# MicroController.net
KiCad netlist of a schematic drawn in Altium Designer
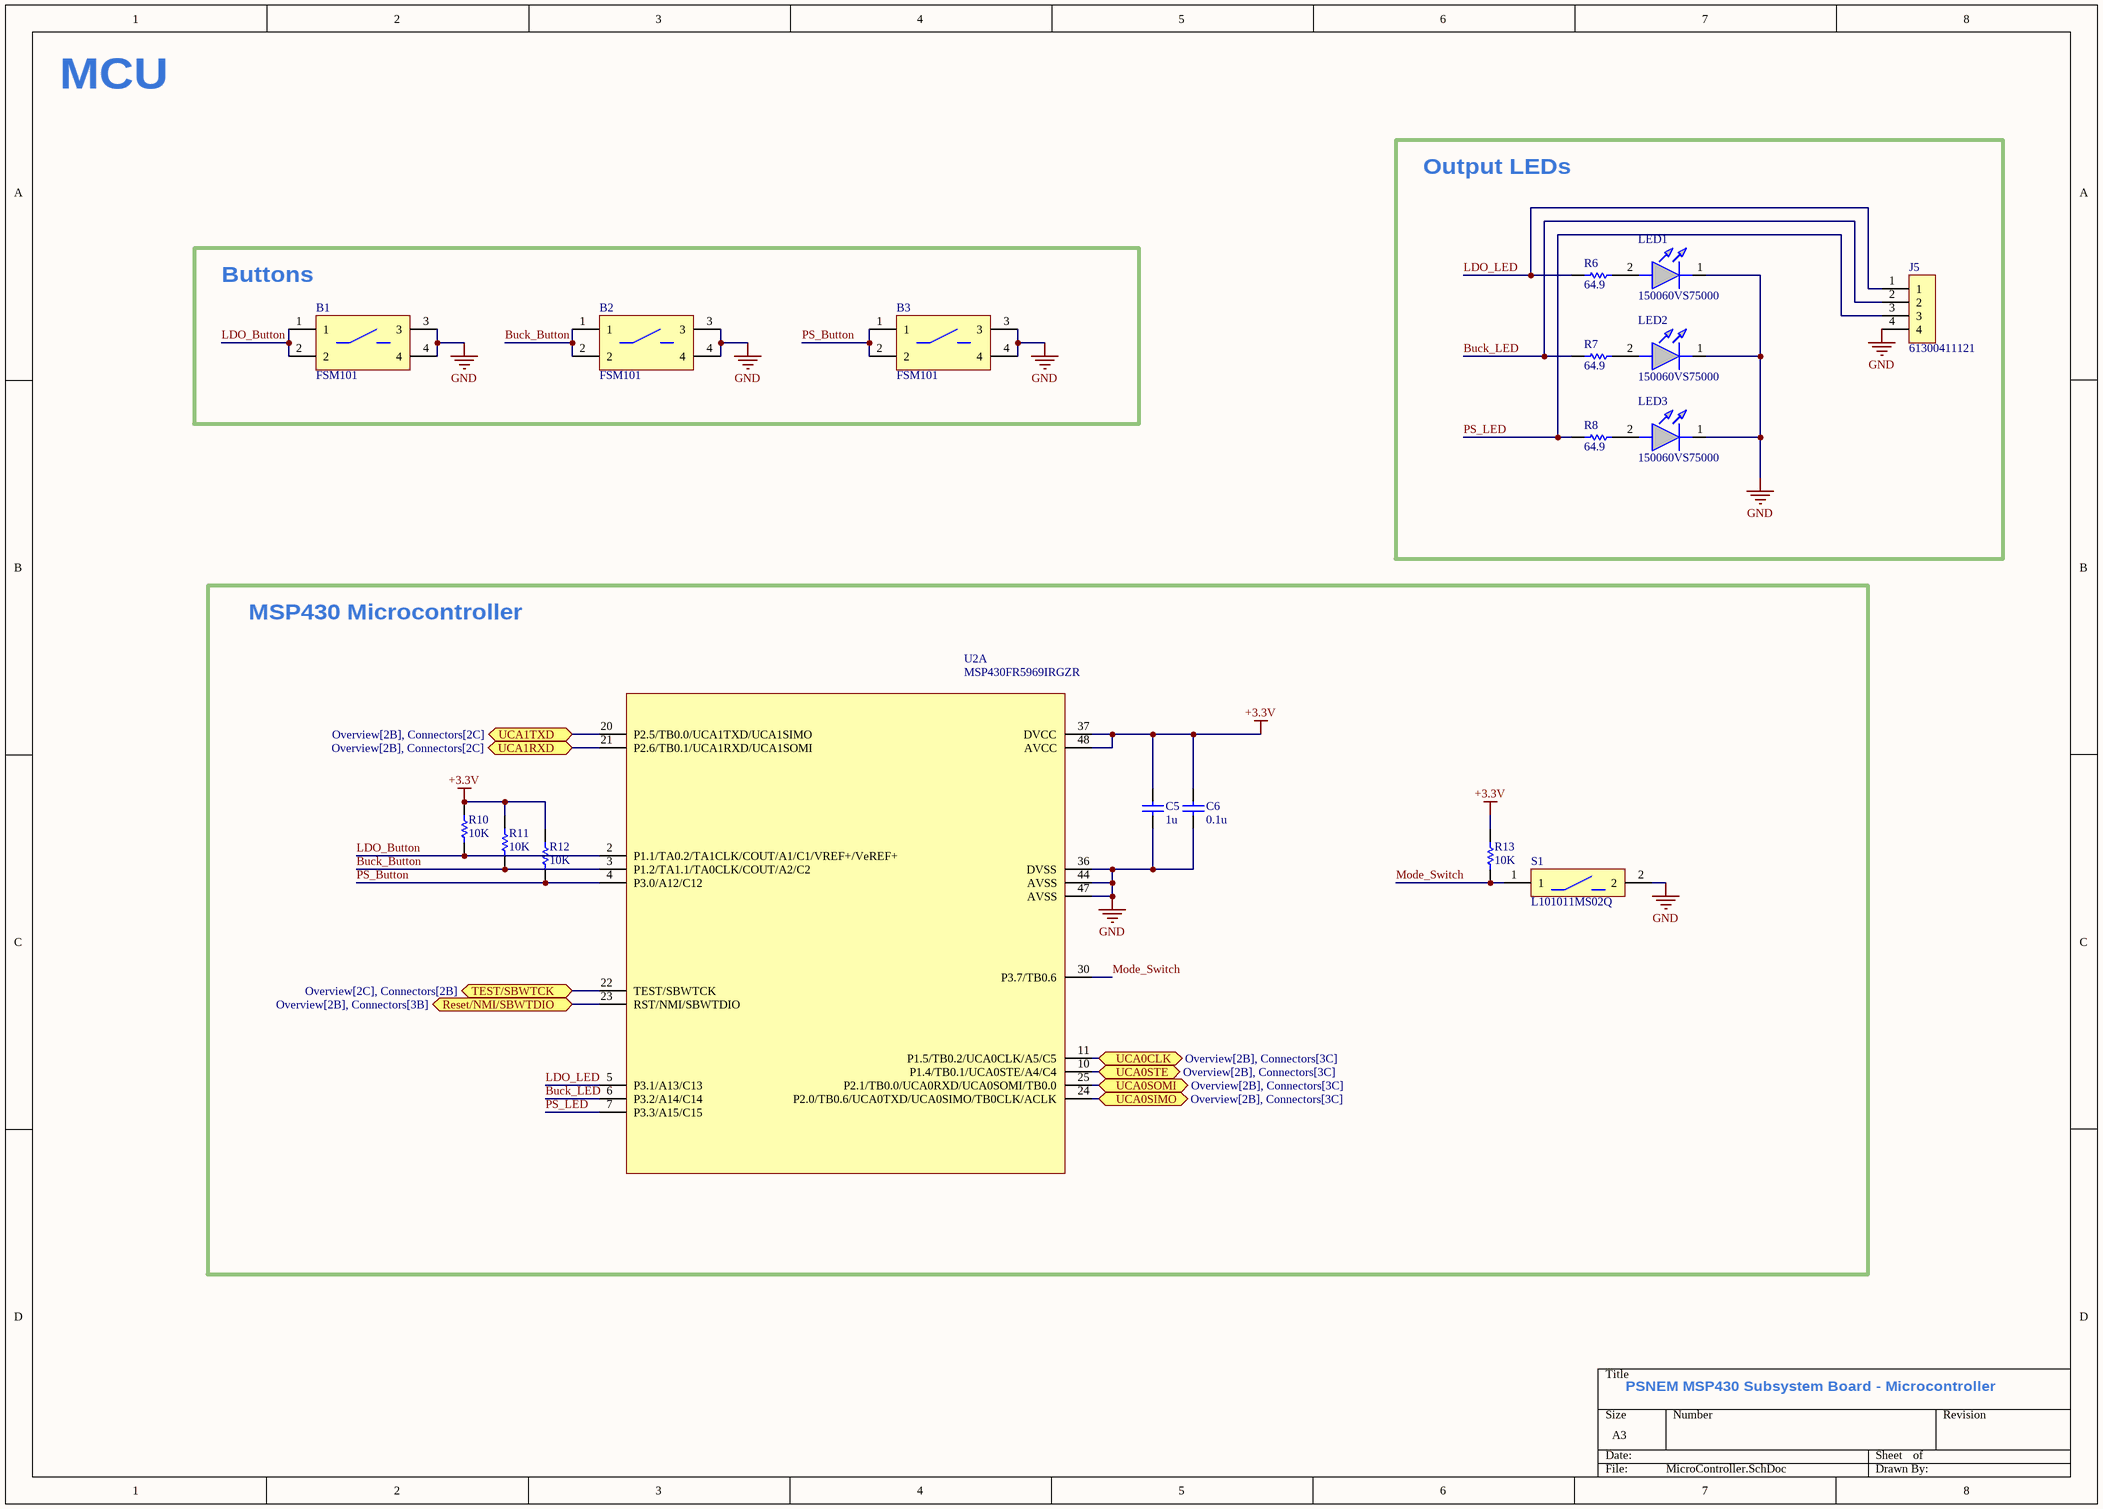
[diagram p0: MicroController.SchDoc]

(export (version "E")
  (design (tool "Eeschema 10.0.6"))
  (components
    (comp (ref "B1")
      (value "FSM101")
      (footprint "FSM101")
      (description "Tactile Switch SPST-NO Top Actuated Through Hole")
      (libsource (lib "Schlib1") (part "FSM101"))
    )
    (comp (ref "B2")
      (value "FSM101")
      (footprint "FSM101")
      (description "Tactile Switch SPST-NO Top Actuated Through Hole")
      (libsource (lib "Schlib1") (part "FSM101"))
    )
    (comp (ref "B3")
      (value "FSM101")
      (footprint "FSM101")
      (description "Tactile Switch SPST-NO Top Actuated Through Hole")
      (libsource (lib "Schlib1") (part "FSM101"))
    )
    (comp (ref "C5")
      (value "1u")
      (footprint "0805 Cap")
      (description "1 µF ±10% 16V Ceramic Capacitor X7R 0805 (2012 Metric)")
      (libsource (lib "Schlib1") (part "CC0805KKX7R7BB105"))
    )
    (comp (ref "C6")
      (value "0.1u")
      (footprint "0805 Cap")
      (description "0.1 µF ±10% 50V Ceramic Capacitor X7R 0805 (2012 Metric)")
      (libsource (lib "Schlib1") (part "CC0805KRX7R9BB104"))
    )
    (comp (ref "J5")
      (value "61300411121")
      (footprint "61300411121")
      (description "Connector Header Through Hole 4 position 0.100\" (2.54mm)")
      (libsource (lib "Schlib1") (part "61300411121"))
    )
    (comp (ref "LED1")
      (value "150060VS75000")
      (footprint "150060VS75000")
      (description "LED GREEN CLEAR 0603 SMD")
      (libsource (lib "Schlib1") (part "150060VS75000"))
    )
    (comp (ref "LED2")
      (value "150060VS75000")
      (footprint "150060VS75000")
      (description "LED GREEN CLEAR 0603 SMD")
      (libsource (lib "Schlib1") (part "150060VS75000"))
    )
    (comp (ref "LED3")
      (value "150060VS75000")
      (footprint "150060VS75000")
      (description "LED GREEN CLEAR 0603 SMD")
      (libsource (lib "Schlib1") (part "150060VS75000"))
    )
    (comp (ref "R6")
      (value "64.9")
      (footprint "RESC1608X06N")
      (description "Thin Film Resistors - SMD 0603 64.9ohm 0.1% 25ppm")
      (libsource (lib "Schlib1") (part "ERA-3AEB64R9V"))
    )
    (comp (ref "R7")
      (value "64.9")
      (footprint "RESC1608X06N")
      (description "Thin Film Resistors - SMD 0603 64.9ohm 0.1% 25ppm")
      (libsource (lib "Schlib1") (part "ERA-3AEB64R9V"))
    )
    (comp (ref "R8")
      (value "64.9")
      (footprint "RESC1608X06N")
      (description "Thin Film Resistors - SMD 0603 64.9ohm 0.1% 25ppm")
      (libsource (lib "Schlib1") (part "ERA-3AEB64R9V"))
    )
    (comp (ref "R10")
      (value "10K")
      (footprint "RESC1608X06N")
      (description "RES SMD 10K OHM 1% 1/3W 0603")
      (libsource (lib "Schlib1") (part "CRCW060310K0FKEAHP"))
    )
    (comp (ref "R11")
      (value "10K")
      (footprint "RESC1608X06N")
      (description "RES SMD 10K OHM 1% 1/3W 0603")
      (libsource (lib "Schlib1") (part "CRCW060310K0FKEAHP"))
    )
    (comp (ref "R12")
      (value "10K")
      (footprint "RESC1608X06N")
      (description "RES SMD 10K OHM 1% 1/3W 0603")
      (libsource (lib "Schlib1") (part "CRCW060310K0FKEAHP"))
    )
    (comp (ref "R13")
      (value "10K")
      (footprint "RESC1608X06N")
      (description "RES SMD 10K OHM 1% 1/3W 0603")
      (libsource (lib "Schlib1") (part "CRCW060310K0FKEAHP"))
    )
    (comp (ref "S1")
      (value "L101011MS02Q")
      (footprint "L101011MS02Q")
      (description "SWITCH SLIDE SPST 4A 125V")
      (libsource (lib "Schlib1") (part "L101011MS02Q"))
    )
    (comp (ref "U2")
      (value "MSP430FR5969IRGZR")
      (footprint "MSP430FR5969IRGZR")
      (description "MSP430 CPUXV2 MSP430™ FRAM Microcontroller IC 16-Bit 16MHz 64KB (64K x 8) FRAM 48-VQFN (7x7)")
      (libsource (lib "Schlib1") (part "MSP430FR5969IRGZR"))
    )
  )
  (nets
    (net (code "1") (name "+3.3V") (class "Default")
      (node (ref "C5") (pin "2") (pinfunction "2_2") (pintype "passive"))
      (node (ref "C6") (pin "2") (pinfunction "2_2") (pintype "passive"))
      (node (ref "R10") (pin "2") (pinfunction "2_2") (pintype "passive"))
      (node (ref "R11") (pin "2") (pinfunction "2_2") (pintype "passive"))
      (node (ref "R12") (pin "2") (pinfunction "2_2") (pintype "passive"))
      (node (ref "R13") (pin "2") (pinfunction "2_2") (pintype "passive"))
      (node (ref "U2") (pin "37") (pinfunction "DVCC_37") (pintype "passive"))
      (node (ref "U2") (pin "48") (pinfunction "AVCC_48") (pintype "passive"))
    )
    (net (code "2") (name "/Buck_Button") (class "Default")
      (node (ref "B2") (pin "1") (pinfunction "1_1") (pintype "passive"))
      (node (ref "B2") (pin "2") (pinfunction "2_2") (pintype "passive"))
      (node (ref "R11") (pin "1") (pinfunction "1_1") (pintype "passive"))
      (node (ref "U2") (pin "3") (pinfunction "P1.2/TA1.1/TA0CLK/COUT/A2/C2_3") (pintype "passive"))
    )
    (net (code "3") (name "/Buck_LED") (class "Default")
      (node (ref "J5") (pin "2") (pinfunction "2_2") (pintype "passive"))
      (node (ref "R7") (pin "1") (pinfunction "1_1") (pintype "passive"))
      (node (ref "U2") (pin "6") (pinfunction "P3.2/A14/C14_6") (pintype "passive"))
    )
    (net (code "4") (name "/LDO_Button") (class "Default")
      (node (ref "B1") (pin "1") (pinfunction "1_1") (pintype "passive"))
      (node (ref "B1") (pin "2") (pinfunction "2_2") (pintype "passive"))
      (node (ref "R10") (pin "1") (pinfunction "1_1") (pintype "passive"))
      (node (ref "U2") (pin "2") (pinfunction "P1.1/TA0.2/TA1CLK/COUT/A1/C1/VREF+/VeREF+_2") (pintype "passive"))
    )
    (net (code "5") (name "/LDO_LED") (class "Default")
      (node (ref "J5") (pin "1") (pinfunction "1_1") (pintype "passive"))
      (node (ref "R6") (pin "1") (pinfunction "1_1") (pintype "passive"))
      (node (ref "U2") (pin "5") (pinfunction "P3.1/A13/C13_5") (pintype "passive"))
    )
    (net (code "6") (name "/Mode_Switch") (class "Default")
      (node (ref "R13") (pin "1") (pinfunction "1_1") (pintype "passive"))
      (node (ref "S1") (pin "1") (pinfunction "1_1") (pintype "passive"))
      (node (ref "U2") (pin "30") (pinfunction "P3.7/TB0.6_30") (pintype "passive"))
    )
    (net (code "7") (name "/PS_Button") (class "Default")
      (node (ref "B3") (pin "1") (pinfunction "1_1") (pintype "passive"))
      (node (ref "B3") (pin "2") (pinfunction "2_2") (pintype "passive"))
      (node (ref "R12") (pin "1") (pinfunction "1_1") (pintype "passive"))
      (node (ref "U2") (pin "4") (pinfunction "P3.0/A12/C12_4") (pintype "passive"))
    )
    (net (code "8") (name "/PS_LED") (class "Default")
      (node (ref "J5") (pin "3") (pinfunction "3_3") (pintype "passive"))
      (node (ref "R8") (pin "1") (pinfunction "1_1") (pintype "passive"))
      (node (ref "U2") (pin "7") (pinfunction "P3.3/A15/C15_7") (pintype "passive"))
    )
    (net (code "9") (name "/Reset{slash}NMI{slash}SBWTDIO") (class "Default")
      (node (ref "U2") (pin "23") (pinfunction "RST/NMI/SBWTDIO_23") (pintype "passive"))
    )
    (net (code "10") (name "/TEST{slash}SBWTCK") (class "Default")
      (node (ref "U2") (pin "22") (pinfunction "TEST/SBWTCK_22") (pintype "passive"))
    )
    (net (code "11") (name "/UCA0CLK") (class "Default")
      (node (ref "U2") (pin "11") (pinfunction "P1.5/TB0.2/UCA0CLK/A5/C5_11") (pintype "passive"))
    )
    (net (code "12") (name "/UCA0SIMO") (class "Default")
      (node (ref "U2") (pin "24") (pinfunction "P2.0/TB0.6/UCA0TXD/UCA0SIMO/TB0CLK/ACLK_24") (pintype "passive"))
    )
    (net (code "13") (name "/UCA0SOMI") (class "Default")
      (node (ref "U2") (pin "25") (pinfunction "P2.1/TB0.0/UCA0RXD/UCA0SOMI/TB0.0_25") (pintype "passive"))
    )
    (net (code "14") (name "/UCA0STE") (class "Default")
      (node (ref "U2") (pin "10") (pinfunction "P1.4/TB0.1/UCA0STE/A4/C4_10") (pintype "passive"))
    )
    (net (code "15") (name "/UCA1RXD") (class "Default")
      (node (ref "U2") (pin "21") (pinfunction "P2.6/TB0.1/UCA1RXD/UCA1SOMI_21") (pintype "passive"))
    )
    (net (code "16") (name "/UCA1TXD") (class "Default")
      (node (ref "U2") (pin "20") (pinfunction "P2.5/TB0.0/UCA1TXD/UCA1SIMO_20") (pintype "passive"))
    )
    (net (code "17") (name "GND") (class "Default")
      (node (ref "B1") (pin "3") (pinfunction "3_3") (pintype "passive"))
      (node (ref "B1") (pin "4") (pinfunction "4_4") (pintype "passive"))
      (node (ref "B2") (pin "3") (pinfunction "3_3") (pintype "passive"))
      (node (ref "B2") (pin "4") (pinfunction "4_4") (pintype "passive"))
      (node (ref "B3") (pin "3") (pinfunction "3_3") (pintype "passive"))
      (node (ref "B3") (pin "4") (pinfunction "4_4") (pintype "passive"))
      (node (ref "C5") (pin "1") (pinfunction "1_1") (pintype "passive"))
      (node (ref "C6") (pin "1") (pinfunction "1_1") (pintype "passive"))
      (node (ref "J5") (pin "4") (pinfunction "4_4") (pintype "passive"))
      (node (ref "LED1") (pin "1") (pinfunction "K_1") (pintype "passive"))
      (node (ref "LED2") (pin "1") (pinfunction "K_1") (pintype "passive"))
      (node (ref "LED3") (pin "1") (pinfunction "K_1") (pintype "passive"))
      (node (ref "S1") (pin "2") (pinfunction "2_2") (pintype "passive"))
      (node (ref "U2") (pin "36") (pinfunction "DVSS_36") (pintype "passive"))
      (node (ref "U2") (pin "44") (pinfunction "AVSS_44") (pintype "passive"))
      (node (ref "U2") (pin "47") (pinfunction "AVSS_47") (pintype "passive"))
    )
    (net (code "18") (name "Net-(LED1-A)") (class "Default")
      (node (ref "LED1") (pin "2") (pinfunction "A_2") (pintype "passive"))
      (node (ref "R6") (pin "2") (pinfunction "2_2") (pintype "passive"))
    )
    (net (code "19") (name "Net-(LED2-A)") (class "Default")
      (node (ref "LED2") (pin "2") (pinfunction "A_2") (pintype "passive"))
      (node (ref "R7") (pin "2") (pinfunction "2_2") (pintype "passive"))
    )
    (net (code "20") (name "Net-(LED3-A)") (class "Default")
      (node (ref "LED3") (pin "2") (pinfunction "A_2") (pintype "passive"))
      (node (ref "R8") (pin "2") (pinfunction "2_2") (pintype "passive"))
    )
  )
)
